# CorePort.net
KiCad netlist of a schematic drawn in Altium Designer
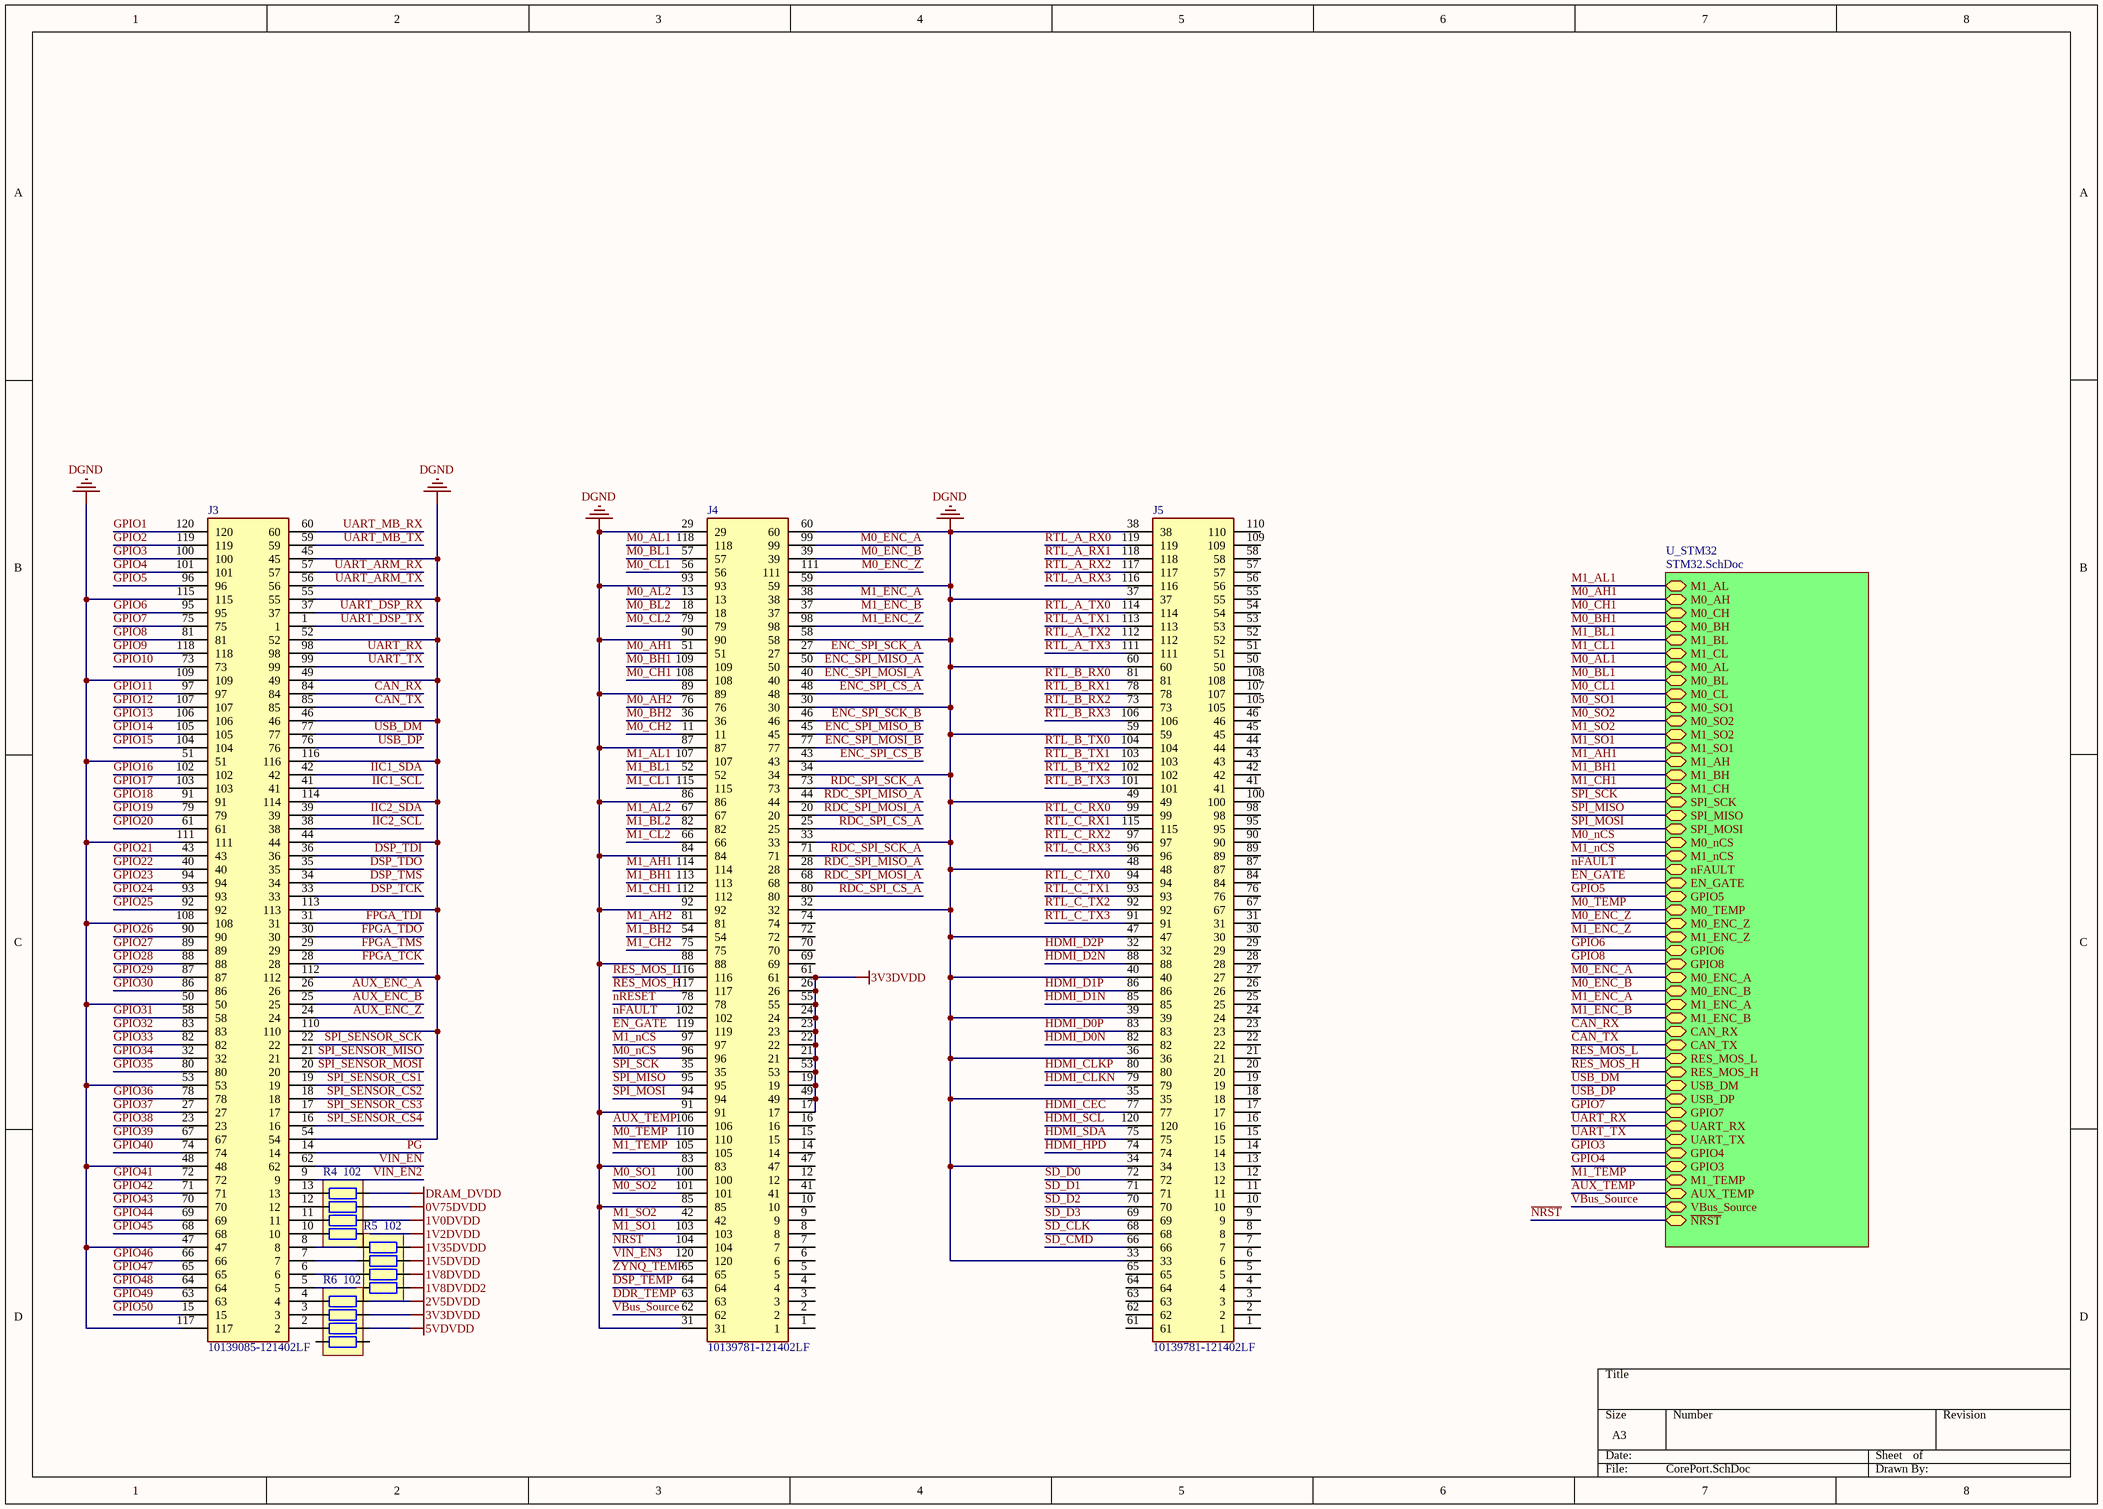
[diagram p0: CorePort.SchDoc]

(export (version "E")
  (design (tool "Eeschema 10.0.6"))
  (components
    (comp (ref "J3")
      (value "10139085-121402LF")
      (footprint "10139085121402LF")
      (description "Connector FE")
      (fields (field (name "MANUFACTURER_PART_NUMBER") "10139781-121402LF"))
      (libsource (lib "SkylakeADSchLib") (part "10139085-121402LF"))
    )
    (comp (ref "J4")
      (value "10139781-121402LF")
      (footprint "SkylakeADPcbLib:10139781121402LF")
      (description "Connector M")
      (libsource (lib "SkylakeADSchLib") (part "10139781-121402LF"))
    )
    (comp (ref "J5")
      (value "10139781-121402LF")
      (footprint "SkylakeADPcbLib:10139781121402LF")
      (description "Connector M")
      (libsource (lib "") (part "10139781-121402LF_1"))
    )
    (comp (ref "R4")
      (value "102")
      (footprint "RCA-8P4R-0603")
      (description "贴片排阻")
      (fields (field (name "版权归属") "封装库来自淘宝 ID：黄晶宝石"))
      (libsource (lib "0.1 - 电阻-电容-电感") (part "R-8P4R"))
    )
    (comp (ref "R5")
      (value "102")
      (footprint "RCA-8P4R-0603")
      (description "贴片排阻")
      (fields (field (name "版权归属") "封装库来自淘宝 ID：黄晶宝石"))
      (libsource (lib "0.1 - 电阻-电容-电感") (part "R-8P4R"))
    )
    (comp (ref "R6")
      (value "102")
      (footprint "RCA-8P4R-0603")
      (description "贴片排阻")
      (fields (field (name "版权归属") "封装库来自淘宝 ID：黄晶宝石"))
      (libsource (lib "0.1 - 电阻-电容-电感") (part "R-8P4R"))
    )
  )
  (nets
    (net (code "1") (name "/AUX_ENC_A") (class "Default")
      (node (ref "J3") (pin "26") (pinfunction "26_26") (pintype "passive"))
    )
    (net (code "2") (name "/AUX_ENC_B") (class "Default")
      (node (ref "J3") (pin "25") (pinfunction "25_25") (pintype "passive"))
    )
    (net (code "3") (name "/AUX_ENC_Z") (class "Default")
      (node (ref "J3") (pin "24") (pinfunction "24_24") (pintype "passive"))
    )
    (net (code "4") (name "/AUX_TEMP") (class "Default")
      (node (ref "J4") (pin "106") (pinfunction "106_106") (pintype "passive"))
    )
    (net (code "5") (name "/CAN_RX") (class "Default")
      (node (ref "J3") (pin "84") (pinfunction "84_84") (pintype "passive"))
    )
    (net (code "6") (name "/CAN_TX") (class "Default")
      (node (ref "J3") (pin "85") (pinfunction "85_85") (pintype "passive"))
    )
    (net (code "7") (name "/DDR_TEMP") (class "Default")
      (node (ref "J4") (pin "63") (pinfunction "63_63") (pintype "passive"))
    )
    (net (code "8") (name "/DSP_TCK") (class "Default")
      (node (ref "J3") (pin "33") (pinfunction "33_33") (pintype "passive"))
    )
    (net (code "9") (name "/DSP_TDI") (class "Default")
      (node (ref "J3") (pin "36") (pinfunction "36_36") (pintype "passive"))
    )
    (net (code "10") (name "/DSP_TDO") (class "Default")
      (node (ref "J3") (pin "35") (pinfunction "35_35") (pintype "passive"))
    )
    (net (code "11") (name "/DSP_TEMP") (class "Default")
      (node (ref "J4") (pin "64") (pinfunction "64_64") (pintype "passive"))
    )
    (net (code "12") (name "/DSP_TMS") (class "Default")
      (node (ref "J3") (pin "34") (pinfunction "34_34") (pintype "passive"))
    )
    (net (code "13") (name "/ENC_SPI_CS_A") (class "Default")
      (node (ref "J4") (pin "48") (pinfunction "48_48") (pintype "passive"))
    )
    (net (code "14") (name "/ENC_SPI_CS_B") (class "Default")
      (node (ref "J4") (pin "43") (pinfunction "43_43") (pintype "passive"))
    )
    (net (code "15") (name "/ENC_SPI_MISO_A") (class "Default")
      (node (ref "J4") (pin "50") (pinfunction "50_50") (pintype "passive"))
    )
    (net (code "16") (name "/ENC_SPI_MISO_B") (class "Default")
      (node (ref "J4") (pin "45") (pinfunction "45_45") (pintype "passive"))
    )
    (net (code "17") (name "/ENC_SPI_MOSI_A") (class "Default")
      (node (ref "J4") (pin "40") (pinfunction "40_40") (pintype "passive"))
    )
    (net (code "18") (name "/ENC_SPI_MOSI_B") (class "Default")
      (node (ref "J4") (pin "77") (pinfunction "77_77") (pintype "passive"))
    )
    (net (code "19") (name "/ENC_SPI_SCK_A") (class "Default")
      (node (ref "J4") (pin "27") (pinfunction "27_27") (pintype "passive"))
    )
    (net (code "20") (name "/ENC_SPI_SCK_B") (class "Default")
      (node (ref "J4") (pin "46") (pinfunction "46_46") (pintype "passive"))
    )
    (net (code "21") (name "/EN_GATE") (class "Default")
      (node (ref "J4") (pin "119") (pinfunction "119_119") (pintype "passive"))
    )
    (net (code "22") (name "/FPGA_TCK") (class "Default")
      (node (ref "J3") (pin "28") (pinfunction "28_28") (pintype "passive"))
    )
    (net (code "23") (name "/FPGA_TDI") (class "Default")
      (node (ref "J3") (pin "31") (pinfunction "31_31") (pintype "passive"))
    )
    (net (code "24") (name "/FPGA_TDO") (class "Default")
      (node (ref "J3") (pin "30") (pinfunction "30_30") (pintype "passive"))
    )
    (net (code "25") (name "/FPGA_TMS") (class "Default")
      (node (ref "J3") (pin "29") (pinfunction "29_29") (pintype "passive"))
    )
    (net (code "26") (name "/GPIO1") (class "Default")
      (node (ref "J3") (pin "120") (pinfunction "120_120") (pintype "passive"))
    )
    (net (code "27") (name "/GPIO2") (class "Default")
      (node (ref "J3") (pin "119") (pinfunction "119_119") (pintype "passive"))
    )
    (net (code "28") (name "/GPIO3") (class "Default")
      (node (ref "J3") (pin "100") (pinfunction "100_100") (pintype "passive"))
    )
    (net (code "29") (name "/GPIO4") (class "Default")
      (node (ref "J3") (pin "101") (pinfunction "101_101") (pintype "passive"))
    )
    (net (code "30") (name "/GPIO5") (class "Default")
      (node (ref "J3") (pin "96") (pinfunction "96_96") (pintype "passive"))
    )
    (net (code "31") (name "/GPIO6") (class "Default")
      (node (ref "J3") (pin "95") (pinfunction "95_95") (pintype "passive"))
    )
    (net (code "32") (name "/GPIO7") (class "Default")
      (node (ref "J3") (pin "75") (pinfunction "75_75") (pintype "passive"))
    )
    (net (code "33") (name "/GPIO8") (class "Default")
      (node (ref "J3") (pin "81") (pinfunction "81_81") (pintype "passive"))
    )
    (net (code "34") (name "/GPIO9") (class "Default")
      (node (ref "J3") (pin "118") (pinfunction "118_118") (pintype "passive"))
    )
    (net (code "35") (name "/GPIO10") (class "Default")
      (node (ref "J3") (pin "73") (pinfunction "73_73") (pintype "passive"))
    )
    (net (code "36") (name "/GPIO11") (class "Default")
      (node (ref "J3") (pin "97") (pinfunction "97_97") (pintype "passive"))
    )
    (net (code "37") (name "/GPIO12") (class "Default")
      (node (ref "J3") (pin "107") (pinfunction "107_107") (pintype "passive"))
    )
    (net (code "38") (name "/GPIO13") (class "Default")
      (node (ref "J3") (pin "106") (pinfunction "106_106") (pintype "passive"))
    )
    (net (code "39") (name "/GPIO14") (class "Default")
      (node (ref "J3") (pin "105") (pinfunction "105_105") (pintype "passive"))
    )
    (net (code "40") (name "/GPIO15") (class "Default")
      (node (ref "J3") (pin "104") (pinfunction "104_104") (pintype "passive"))
    )
    (net (code "41") (name "/GPIO16") (class "Default")
      (node (ref "J3") (pin "102") (pinfunction "102_102") (pintype "passive"))
    )
    (net (code "42") (name "/GPIO17") (class "Default")
      (node (ref "J3") (pin "103") (pinfunction "103_103") (pintype "passive"))
    )
    (net (code "43") (name "/GPIO18") (class "Default")
      (node (ref "J3") (pin "91") (pinfunction "91_91") (pintype "passive"))
    )
    (net (code "44") (name "/GPIO19") (class "Default")
      (node (ref "J3") (pin "79") (pinfunction "79_79") (pintype "passive"))
    )
    (net (code "45") (name "/GPIO20") (class "Default")
      (node (ref "J3") (pin "61") (pinfunction "61_61") (pintype "passive"))
    )
    (net (code "46") (name "/GPIO21") (class "Default")
      (node (ref "J3") (pin "43") (pinfunction "43_43") (pintype "passive"))
    )
    (net (code "47") (name "/GPIO22") (class "Default")
      (node (ref "J3") (pin "40") (pinfunction "40_40") (pintype "passive"))
    )
    (net (code "48") (name "/GPIO23") (class "Default")
      (node (ref "J3") (pin "94") (pinfunction "94_94") (pintype "passive"))
    )
    (net (code "49") (name "/GPIO24") (class "Default")
      (node (ref "J3") (pin "93") (pinfunction "93_93") (pintype "passive"))
    )
    (net (code "50") (name "/GPIO25") (class "Default")
      (node (ref "J3") (pin "92") (pinfunction "92_92") (pintype "passive"))
    )
    (net (code "51") (name "/GPIO26") (class "Default")
      (node (ref "J3") (pin "90") (pinfunction "90_90") (pintype "passive"))
    )
    (net (code "52") (name "/GPIO27") (class "Default")
      (node (ref "J3") (pin "89") (pinfunction "89_89") (pintype "passive"))
    )
    (net (code "53") (name "/GPIO28") (class "Default")
      (node (ref "J3") (pin "88") (pinfunction "88_88") (pintype "passive"))
    )
    (net (code "54") (name "/GPIO29") (class "Default")
      (node (ref "J3") (pin "87") (pinfunction "87_87") (pintype "passive"))
    )
    (net (code "55") (name "/GPIO30") (class "Default")
      (node (ref "J3") (pin "86") (pinfunction "86_86") (pintype "passive"))
    )
    (net (code "56") (name "/GPIO31") (class "Default")
      (node (ref "J3") (pin "58") (pinfunction "58_58") (pintype "passive"))
    )
    (net (code "57") (name "/GPIO32") (class "Default")
      (node (ref "J3") (pin "83") (pinfunction "83_83") (pintype "passive"))
    )
    (net (code "58") (name "/GPIO33") (class "Default")
      (node (ref "J3") (pin "82") (pinfunction "82_82") (pintype "passive"))
    )
    (net (code "59") (name "/GPIO34") (class "Default")
      (node (ref "J3") (pin "32") (pinfunction "32_32") (pintype "passive"))
    )
    (net (code "60") (name "/GPIO35") (class "Default")
      (node (ref "J3") (pin "80") (pinfunction "80_80") (pintype "passive"))
    )
    (net (code "61") (name "/GPIO36") (class "Default")
      (node (ref "J3") (pin "78") (pinfunction "78_78") (pintype "passive"))
    )
    (net (code "62") (name "/GPIO37") (class "Default")
      (node (ref "J3") (pin "27") (pinfunction "27_27") (pintype "passive"))
    )
    (net (code "63") (name "/GPIO38") (class "Default")
      (node (ref "J3") (pin "23") (pinfunction "23_23") (pintype "passive"))
    )
    (net (code "64") (name "/GPIO39") (class "Default")
      (node (ref "J3") (pin "67") (pinfunction "67_67") (pintype "passive"))
    )
    (net (code "65") (name "/GPIO40") (class "Default")
      (node (ref "J3") (pin "74") (pinfunction "74_74") (pintype "passive"))
    )
    (net (code "66") (name "/GPIO41") (class "Default")
      (node (ref "J3") (pin "72") (pinfunction "72_72") (pintype "passive"))
    )
    (net (code "67") (name "/GPIO42") (class "Default")
      (node (ref "J3") (pin "71") (pinfunction "71_71") (pintype "passive"))
    )
    (net (code "68") (name "/GPIO43") (class "Default")
      (node (ref "J3") (pin "70") (pinfunction "70_70") (pintype "passive"))
    )
    (net (code "69") (name "/GPIO44") (class "Default")
      (node (ref "J3") (pin "69") (pinfunction "69_69") (pintype "passive"))
    )
    (net (code "70") (name "/GPIO45") (class "Default")
      (node (ref "J3") (pin "68") (pinfunction "68_68") (pintype "passive"))
    )
    (net (code "71") (name "/GPIO46") (class "Default")
      (node (ref "J3") (pin "66") (pinfunction "66_66") (pintype "passive"))
    )
    (net (code "72") (name "/GPIO47") (class "Default")
      (node (ref "J3") (pin "65") (pinfunction "65_65") (pintype "passive"))
    )
    (net (code "73") (name "/GPIO48") (class "Default")
      (node (ref "J3") (pin "64") (pinfunction "64_64") (pintype "passive"))
    )
    (net (code "74") (name "/GPIO49") (class "Default")
      (node (ref "J3") (pin "63") (pinfunction "63_63") (pintype "passive"))
    )
    (net (code "75") (name "/GPIO50") (class "Default")
      (node (ref "J3") (pin "15") (pinfunction "15_15") (pintype "passive"))
    )
    (net (code "76") (name "/HDMI_CEC") (class "Default")
      (node (ref "J5") (pin "77") (pinfunction "77_77") (pintype "passive"))
    )
    (net (code "77") (name "/HDMI_CLKN") (class "Default")
      (node (ref "J5") (pin "79") (pinfunction "79_79") (pintype "passive"))
    )
    (net (code "78") (name "/HDMI_CLKP") (class "Default")
      (node (ref "J5") (pin "80") (pinfunction "80_80") (pintype "passive"))
    )
    (net (code "79") (name "/HDMI_D0N") (class "Default")
      (node (ref "J5") (pin "82") (pinfunction "82_82") (pintype "passive"))
    )
    (net (code "80") (name "/HDMI_D0P") (class "Default")
      (node (ref "J5") (pin "83") (pinfunction "83_83") (pintype "passive"))
    )
    (net (code "81") (name "/HDMI_D1N") (class "Default")
      (node (ref "J5") (pin "85") (pinfunction "85_85") (pintype "passive"))
    )
    (net (code "82") (name "/HDMI_D1P") (class "Default")
      (node (ref "J5") (pin "86") (pinfunction "86_86") (pintype "passive"))
    )
    (net (code "83") (name "/HDMI_D2N") (class "Default")
      (node (ref "J5") (pin "88") (pinfunction "88_88") (pintype "passive"))
    )
    (net (code "84") (name "/HDMI_D2P") (class "Default")
      (node (ref "J5") (pin "32") (pinfunction "32_32") (pintype "passive"))
    )
    (net (code "85") (name "/HDMI_HPD") (class "Default")
      (node (ref "J5") (pin "74") (pinfunction "74_74") (pintype "passive"))
    )
    (net (code "86") (name "/HDMI_SCL") (class "Default")
      (node (ref "J5") (pin "120") (pinfunction "120_120") (pintype "passive"))
    )
    (net (code "87") (name "/HDMI_SDA") (class "Default")
      (node (ref "J5") (pin "75") (pinfunction "75_75") (pintype "passive"))
    )
    (net (code "88") (name "/IIC1_SCL") (class "Default")
      (node (ref "J3") (pin "41") (pinfunction "41_41") (pintype "passive"))
    )
    (net (code "89") (name "/IIC1_SDA") (class "Default")
      (node (ref "J3") (pin "42") (pinfunction "42_42") (pintype "passive"))
    )
    (net (code "90") (name "/IIC2_SCL") (class "Default")
      (node (ref "J3") (pin "38") (pinfunction "38_38") (pintype "passive"))
    )
    (net (code "91") (name "/IIC2_SDA") (class "Default")
      (node (ref "J3") (pin "39") (pinfunction "39_39") (pintype "passive"))
    )
    (net (code "92") (name "/M0_AH1") (class "Default")
      (node (ref "J4") (pin "51") (pinfunction "51_51") (pintype "passive"))
    )
    (net (code "93") (name "/M0_AH2") (class "Default")
      (node (ref "J4") (pin "76") (pinfunction "76_76") (pintype "passive"))
    )
    (net (code "94") (name "/M0_AL1") (class "Default")
      (node (ref "J4") (pin "118") (pinfunction "118_118") (pintype "passive"))
    )
    (net (code "95") (name "/M0_AL2") (class "Default")
      (node (ref "J4") (pin "13") (pinfunction "13_13") (pintype "passive"))
    )
    (net (code "96") (name "/M0_BH1") (class "Default")
      (node (ref "J4") (pin "109") (pinfunction "109_109") (pintype "passive"))
    )
    (net (code "97") (name "/M0_BH2") (class "Default")
      (node (ref "J4") (pin "36") (pinfunction "36_36") (pintype "passive"))
    )
    (net (code "98") (name "/M0_BL1") (class "Default")
      (node (ref "J4") (pin "57") (pinfunction "57_57") (pintype "passive"))
    )
    (net (code "99") (name "/M0_BL2") (class "Default")
      (node (ref "J4") (pin "18") (pinfunction "18_18") (pintype "passive"))
    )
    (net (code "100") (name "/M0_CH1") (class "Default")
      (node (ref "J4") (pin "108") (pinfunction "108_108") (pintype "passive"))
    )
    (net (code "101") (name "/M0_CH2") (class "Default")
      (node (ref "J4") (pin "11") (pinfunction "11_11") (pintype "passive"))
    )
    (net (code "102") (name "/M0_CL1") (class "Default")
      (node (ref "J4") (pin "56") (pinfunction "56_56") (pintype "passive"))
    )
    (net (code "103") (name "/M0_CL2") (class "Default")
      (node (ref "J4") (pin "79") (pinfunction "79_79") (pintype "passive"))
    )
    (net (code "104") (name "/M0_ENC_A") (class "Default")
      (node (ref "J4") (pin "99") (pinfunction "99_99") (pintype "passive"))
    )
    (net (code "105") (name "/M0_ENC_B") (class "Default")
      (node (ref "J4") (pin "39") (pinfunction "39_39") (pintype "passive"))
    )
    (net (code "106") (name "/M0_ENC_Z") (class "Default")
      (node (ref "J4") (pin "111") (pinfunction "111_111") (pintype "passive"))
    )
    (net (code "107") (name "/M0_SO1") (class "Default")
      (node (ref "J4") (pin "100") (pinfunction "100_100") (pintype "passive"))
    )
    (net (code "108") (name "/M0_SO2") (class "Default")
      (node (ref "J4") (pin "101") (pinfunction "101_101") (pintype "passive"))
    )
    (net (code "109") (name "/M0_TEMP") (class "Default")
      (node (ref "J4") (pin "110") (pinfunction "110_110") (pintype "passive"))
    )
    (net (code "110") (name "/M0_nCS") (class "Default")
      (node (ref "J4") (pin "96") (pinfunction "96_96") (pintype "passive"))
    )
    (net (code "111") (name "/M1_AH1") (class "Default")
      (node (ref "J4") (pin "114") (pinfunction "114_114") (pintype "passive"))
    )
    (net (code "112") (name "/M1_AH2") (class "Default")
      (node (ref "J4") (pin "81") (pinfunction "81_81") (pintype "passive"))
    )
    (net (code "113") (name "/M1_AL1") (class "Default")
      (node (ref "J4") (pin "107") (pinfunction "107_107") (pintype "passive"))
    )
    (net (code "114") (name "/M1_AL2") (class "Default")
      (node (ref "J4") (pin "67") (pinfunction "67_67") (pintype "passive"))
    )
    (net (code "115") (name "/M1_BH1") (class "Default")
      (node (ref "J4") (pin "113") (pinfunction "113_113") (pintype "passive"))
    )
    (net (code "116") (name "/M1_BH2") (class "Default")
      (node (ref "J4") (pin "54") (pinfunction "54_54") (pintype "passive"))
    )
    (net (code "117") (name "/M1_BL1") (class "Default")
      (node (ref "J4") (pin "52") (pinfunction "52_52") (pintype "passive"))
    )
    (net (code "118") (name "/M1_BL2") (class "Default")
      (node (ref "J4") (pin "82") (pinfunction "82_82") (pintype "passive"))
    )
    (net (code "119") (name "/M1_CH1") (class "Default")
      (node (ref "J4") (pin "112") (pinfunction "112_112") (pintype "passive"))
    )
    (net (code "120") (name "/M1_CH2") (class "Default")
      (node (ref "J4") (pin "75") (pinfunction "75_75") (pintype "passive"))
    )
    (net (code "121") (name "/M1_CL1") (class "Default")
      (node (ref "J4") (pin "115") (pinfunction "115_115") (pintype "passive"))
    )
    (net (code "122") (name "/M1_CL2") (class "Default")
      (node (ref "J4") (pin "66") (pinfunction "66_66") (pintype "passive"))
    )
    (net (code "123") (name "/M1_ENC_A") (class "Default")
      (node (ref "J4") (pin "38") (pinfunction "38_38") (pintype "passive"))
    )
    (net (code "124") (name "/M1_ENC_B") (class "Default")
      (node (ref "J4") (pin "37") (pinfunction "37_37") (pintype "passive"))
    )
    (net (code "125") (name "/M1_ENC_Z") (class "Default")
      (node (ref "J4") (pin "98") (pinfunction "98_98") (pintype "passive"))
    )
    (net (code "126") (name "/M1_SO1") (class "Default")
      (node (ref "J4") (pin "103") (pinfunction "103_103") (pintype "passive"))
    )
    (net (code "127") (name "/M1_SO2") (class "Default")
      (node (ref "J4") (pin "42") (pinfunction "42_42") (pintype "passive"))
    )
    (net (code "128") (name "/M1_TEMP") (class "Default")
      (node (ref "J4") (pin "105") (pinfunction "105_105") (pintype "passive"))
    )
    (net (code "129") (name "/M1_nCS") (class "Default")
      (node (ref "J4") (pin "97") (pinfunction "97_97") (pintype "passive"))
    )
    (net (code "130") (name "/PG") (class "Default")
      (node (ref "J3") (pin "14") (pinfunction "14_14") (pintype "passive"))
    )
    (net (code "131") (name "/RDC_SPI_CS_A") (class "Default")
      (node (ref "J4") (pin "25") (pinfunction "25_25") (pintype "passive"))
      (node (ref "J4") (pin "80") (pinfunction "80_80") (pintype "passive"))
    )
    (net (code "132") (name "/RDC_SPI_MISO_A") (class "Default")
      (node (ref "J4") (pin "28") (pinfunction "28_28") (pintype "passive"))
      (node (ref "J4") (pin "44") (pinfunction "44_44") (pintype "passive"))
    )
    (net (code "133") (name "/RDC_SPI_MOSI_A") (class "Default")
      (node (ref "J4") (pin "20") (pinfunction "20_20") (pintype "passive"))
      (node (ref "J4") (pin "68") (pinfunction "68_68") (pintype "passive"))
    )
    (net (code "134") (name "/RDC_SPI_SCK_A") (class "Default")
      (node (ref "J4") (pin "71") (pinfunction "71_71") (pintype "passive"))
      (node (ref "J4") (pin "73") (pinfunction "73_73") (pintype "passive"))
    )
    (net (code "135") (name "/RES_MOS_H") (class "Default")
      (node (ref "J4") (pin "117") (pinfunction "117_117") (pintype "passive"))
    )
    (net (code "136") (name "/RES_MOS_L") (class "Default")
      (node (ref "J4") (pin "116") (pinfunction "116_116") (pintype "passive"))
    )
    (net (code "137") (name "/RTL_A_RX0") (class "Default")
      (node (ref "J5") (pin "119") (pinfunction "119_119") (pintype "passive"))
    )
    (net (code "138") (name "/RTL_A_RX1") (class "Default")
      (node (ref "J5") (pin "118") (pinfunction "118_118") (pintype "passive"))
    )
    (net (code "139") (name "/RTL_A_RX2") (class "Default")
      (node (ref "J5") (pin "117") (pinfunction "117_117") (pintype "passive"))
    )
    (net (code "140") (name "/RTL_A_RX3") (class "Default")
      (node (ref "J5") (pin "116") (pinfunction "116_116") (pintype "passive"))
    )
    (net (code "141") (name "/RTL_A_TX0") (class "Default")
      (node (ref "J5") (pin "114") (pinfunction "114_114") (pintype "passive"))
    )
    (net (code "142") (name "/RTL_A_TX1") (class "Default")
      (node (ref "J5") (pin "113") (pinfunction "113_113") (pintype "passive"))
    )
    (net (code "143") (name "/RTL_A_TX2") (class "Default")
      (node (ref "J5") (pin "112") (pinfunction "112_112") (pintype "passive"))
    )
    (net (code "144") (name "/RTL_A_TX3") (class "Default")
      (node (ref "J5") (pin "111") (pinfunction "111_111") (pintype "passive"))
    )
    (net (code "145") (name "/RTL_B_RX0") (class "Default")
      (node (ref "J5") (pin "81") (pinfunction "81_81") (pintype "passive"))
    )
    (net (code "146") (name "/RTL_B_RX1") (class "Default")
      (node (ref "J5") (pin "78") (pinfunction "78_78") (pintype "passive"))
    )
    (net (code "147") (name "/RTL_B_RX2") (class "Default")
      (node (ref "J5") (pin "73") (pinfunction "73_73") (pintype "passive"))
    )
    (net (code "148") (name "/RTL_B_RX3") (class "Default")
      (node (ref "J5") (pin "106") (pinfunction "106_106") (pintype "passive"))
    )
    (net (code "149") (name "/RTL_B_TX0") (class "Default")
      (node (ref "J5") (pin "104") (pinfunction "104_104") (pintype "passive"))
    )
    (net (code "150") (name "/RTL_B_TX1") (class "Default")
      (node (ref "J5") (pin "103") (pinfunction "103_103") (pintype "passive"))
    )
    (net (code "151") (name "/RTL_B_TX2") (class "Default")
      (node (ref "J5") (pin "102") (pinfunction "102_102") (pintype "passive"))
    )
    (net (code "152") (name "/RTL_B_TX3") (class "Default")
      (node (ref "J5") (pin "101") (pinfunction "101_101") (pintype "passive"))
    )
    (net (code "153") (name "/RTL_C_RX0") (class "Default")
      (node (ref "J5") (pin "99") (pinfunction "99_99") (pintype "passive"))
    )
    (net (code "154") (name "/RTL_C_RX1") (class "Default")
      (node (ref "J5") (pin "115") (pinfunction "115_115") (pintype "passive"))
    )
    (net (code "155") (name "/RTL_C_RX2") (class "Default")
      (node (ref "J5") (pin "97") (pinfunction "97_97") (pintype "passive"))
    )
    (net (code "156") (name "/RTL_C_RX3") (class "Default")
      (node (ref "J5") (pin "96") (pinfunction "96_96") (pintype "passive"))
    )
    (net (code "157") (name "/RTL_C_TX0") (class "Default")
      (node (ref "J5") (pin "94") (pinfunction "94_94") (pintype "passive"))
    )
    (net (code "158") (name "/RTL_C_TX1") (class "Default")
      (node (ref "J5") (pin "93") (pinfunction "93_93") (pintype "passive"))
    )
    (net (code "159") (name "/RTL_C_TX2") (class "Default")
      (node (ref "J5") (pin "92") (pinfunction "92_92") (pintype "passive"))
    )
    (net (code "160") (name "/RTL_C_TX3") (class "Default")
      (node (ref "J5") (pin "91") (pinfunction "91_91") (pintype "passive"))
    )
    (net (code "161") (name "/SD_CLK") (class "Default")
      (node (ref "J5") (pin "68") (pinfunction "68_68") (pintype "passive"))
    )
    (net (code "162") (name "/SD_CMD") (class "Default")
      (node (ref "J5") (pin "66") (pinfunction "66_66") (pintype "passive"))
    )
    (net (code "163") (name "/SD_D0") (class "Default")
      (node (ref "J5") (pin "72") (pinfunction "72_72") (pintype "passive"))
    )
    (net (code "164") (name "/SD_D1") (class "Default")
      (node (ref "J5") (pin "71") (pinfunction "71_71") (pintype "passive"))
    )
    (net (code "165") (name "/SD_D2") (class "Default")
      (node (ref "J5") (pin "70") (pinfunction "70_70") (pintype "passive"))
    )
    (net (code "166") (name "/SD_D3") (class "Default")
      (node (ref "J5") (pin "69") (pinfunction "69_69") (pintype "passive"))
    )
    (net (code "167") (name "/SPI_MISO") (class "Default")
      (node (ref "J4") (pin "95") (pinfunction "95_95") (pintype "passive"))
    )
    (net (code "168") (name "/SPI_MOSI") (class "Default")
      (node (ref "J4") (pin "94") (pinfunction "94_94") (pintype "passive"))
    )
    (net (code "169") (name "/SPI_SCK") (class "Default")
      (node (ref "J4") (pin "35") (pinfunction "35_35") (pintype "passive"))
    )
    (net (code "170") (name "/SPI_SENSOR_CS1") (class "Default")
      (node (ref "J3") (pin "19") (pinfunction "19_19") (pintype "passive"))
    )
    (net (code "171") (name "/SPI_SENSOR_CS2") (class "Default")
      (node (ref "J3") (pin "18") (pinfunction "18_18") (pintype "passive"))
    )
    (net (code "172") (name "/SPI_SENSOR_CS3") (class "Default")
      (node (ref "J3") (pin "17") (pinfunction "17_17") (pintype "passive"))
    )
    (net (code "173") (name "/SPI_SENSOR_CS4") (class "Default")
      (node (ref "J3") (pin "16") (pinfunction "16_16") (pintype "passive"))
    )
    (net (code "174") (name "/SPI_SENSOR_MISO") (class "Default")
      (node (ref "J3") (pin "21") (pinfunction "21_21") (pintype "passive"))
    )
    (net (code "175") (name "/SPI_SENSOR_MOSI") (class "Default")
      (node (ref "J3") (pin "20") (pinfunction "20_20") (pintype "passive"))
    )
    (net (code "176") (name "/SPI_SENSOR_SCK") (class "Default")
      (node (ref "J3") (pin "22") (pinfunction "22_22") (pintype "passive"))
    )
    (net (code "177") (name "/UART_ARM_RX") (class "Default")
      (node (ref "J3") (pin "57") (pinfunction "57_57") (pintype "passive"))
    )
    (net (code "178") (name "/UART_ARM_TX") (class "Default")
      (node (ref "J3") (pin "56") (pinfunction "56_56") (pintype "passive"))
    )
    (net (code "179") (name "/UART_DSP_RX") (class "Default")
      (node (ref "J3") (pin "37") (pinfunction "37_37") (pintype "passive"))
    )
    (net (code "180") (name "/UART_DSP_TX") (class "Default")
      (node (ref "J3") (pin "1") (pinfunction "1_1") (pintype "passive"))
    )
    (net (code "181") (name "/UART_MB_RX") (class "Default")
      (node (ref "J3") (pin "60") (pinfunction "60_60") (pintype "passive"))
    )
    (net (code "182") (name "/UART_MB_TX") (class "Default")
      (node (ref "J3") (pin "59") (pinfunction "59_59") (pintype "passive"))
    )
    (net (code "183") (name "/UART_RX") (class "Default")
      (node (ref "J3") (pin "98") (pinfunction "98_98") (pintype "passive"))
    )
    (net (code "184") (name "/UART_TX") (class "Default")
      (node (ref "J3") (pin "99") (pinfunction "99_99") (pintype "passive"))
    )
    (net (code "185") (name "/USB_DM") (class "Default")
      (node (ref "J3") (pin "77") (pinfunction "77_77") (pintype "passive"))
    )
    (net (code "186") (name "/USB_DP") (class "Default")
      (node (ref "J3") (pin "76") (pinfunction "76_76") (pintype "passive"))
    )
    (net (code "187") (name "/VBus_Source") (class "Default")
      (node (ref "J4") (pin "62") (pinfunction "62_62") (pintype "passive"))
    )
    (net (code "188") (name "/VIN_EN") (class "Default")
      (node (ref "J3") (pin "62") (pinfunction "62_62") (pintype "passive"))
    )
    (net (code "189") (name "/VIN_EN2") (class "Default")
      (node (ref "J3") (pin "9") (pinfunction "9_9") (pintype "passive"))
    )
    (net (code "190") (name "/VIN_EN3") (class "Default")
      (node (ref "J4") (pin "120") (pinfunction "120_120") (pintype "passive"))
    )
    (net (code "191") (name "/ZYNQ_TEMP") (class "Default")
      (node (ref "J4") (pin "65") (pinfunction "65_65") (pintype "passive"))
    )
    (net (code "192") (name "/nFAULT") (class "Default")
      (node (ref "J4") (pin "102") (pinfunction "102_102") (pintype "passive"))
    )
    (net (code "193") (name "/nRESET") (class "Default")
      (node (ref "J4") (pin "78") (pinfunction "78_78") (pintype "passive"))
    )
    (net (code "194") (name "/~{NRST}") (class "Default")
      (node (ref "J4") (pin "104") (pinfunction "104_104") (pintype "passive"))
    )
    (net (code "195") (name "0V75DVDD") (class "Default")
      (node (ref "R4") (pin "7") (pinfunction "7_7") (pintype "passive"))
    )
    (net (code "196") (name "1V0DVDD") (class "Default")
      (node (ref "R4") (pin "6") (pinfunction "6_6") (pintype "passive"))
    )
    (net (code "197") (name "1V2DVDD") (class "Default")
      (node (ref "R4") (pin "5") (pinfunction "5_5") (pintype "passive"))
    )
    (net (code "198") (name "1V5DVDD") (class "Default")
      (node (ref "R5") (pin "7") (pinfunction "7_7") (pintype "passive"))
    )
    (net (code "199") (name "1V8DVDD") (class "Default")
      (node (ref "R5") (pin "6") (pinfunction "6_6") (pintype "passive"))
    )
    (net (code "200") (name "1V8DVDD2") (class "Default")
      (node (ref "R5") (pin "5") (pinfunction "5_5") (pintype "passive"))
    )
    (net (code "201") (name "1V35DVDD") (class "Default")
      (node (ref "R5") (pin "8") (pinfunction "8_8") (pintype "passive"))
    )
    (net (code "202") (name "2V5DVDD") (class "Default")
      (node (ref "R6") (pin "8") (pinfunction "8_8") (pintype "passive"))
    )
    (net (code "203") (name "3V3DVDD") (class "Default")
      (node (ref "J4") (pin "17") (pinfunction "17_17") (pintype "passive"))
      (node (ref "J4") (pin "19") (pinfunction "19_19") (pintype "passive"))
      (node (ref "J4") (pin "21") (pinfunction "21_21") (pintype "passive"))
      (node (ref "J4") (pin "22") (pinfunction "22_22") (pintype "passive"))
      (node (ref "J4") (pin "23") (pinfunction "23_23") (pintype "passive"))
      (node (ref "J4") (pin "24") (pinfunction "24_24") (pintype "passive"))
      (node (ref "J4") (pin "26") (pinfunction "26_26") (pintype "passive"))
      (node (ref "J4") (pin "49") (pinfunction "49_49") (pintype "passive"))
      (node (ref "J4") (pin "53") (pinfunction "53_53") (pintype "passive"))
      (node (ref "J4") (pin "55") (pinfunction "55_55") (pintype "passive"))
      (node (ref "J4") (pin "61") (pinfunction "61_61") (pintype "passive"))
      (node (ref "R6") (pin "7") (pinfunction "7_7") (pintype "passive"))
    )
    (net (code "204") (name "5VDVDD") (class "Default")
      (node (ref "R6") (pin "6") (pinfunction "6_6") (pintype "passive"))
    )
    (net (code "205") (name "DGND") (class "Default")
      (node (ref "J3") (pin "108") (pinfunction "108_108") (pintype "passive"))
      (node (ref "J3") (pin "109") (pinfunction "109_109") (pintype "passive"))
      (node (ref "J3") (pin "110") (pinfunction "110_110") (pintype "passive"))
      (node (ref "J3") (pin "111") (pinfunction "111_111") (pintype "passive"))
      (node (ref "J3") (pin "112") (pinfunction "112_112") (pintype "passive"))
      (node (ref "J3") (pin "113") (pinfunction "113_113") (pintype "passive"))
      (node (ref "J3") (pin "114") (pinfunction "114_114") (pintype "passive"))
      (node (ref "J3") (pin "115") (pinfunction "115_115") (pintype "passive"))
      (node (ref "J3") (pin "116") (pinfunction "116_116") (pintype "passive"))
      (node (ref "J3") (pin "117") (pinfunction "117_117") (pintype "passive"))
      (node (ref "J3") (pin "44") (pinfunction "44_44") (pintype "passive"))
      (node (ref "J3") (pin "45") (pinfunction "45_45") (pintype "passive"))
      (node (ref "J3") (pin "46") (pinfunction "46_46") (pintype "passive"))
      (node (ref "J3") (pin "47") (pinfunction "47_47") (pintype "passive"))
      (node (ref "J3") (pin "48") (pinfunction "48_48") (pintype "passive"))
      (node (ref "J3") (pin "49") (pinfunction "49_49") (pintype "passive"))
      (node (ref "J3") (pin "50") (pinfunction "50_50") (pintype "passive"))
      (node (ref "J3") (pin "51") (pinfunction "51_51") (pintype "passive"))
      (node (ref "J3") (pin "52") (pinfunction "52_52") (pintype "passive"))
      (node (ref "J3") (pin "53") (pinfunction "53_53") (pintype "passive"))
      (node (ref "J3") (pin "54") (pinfunction "54_54") (pintype "passive"))
      (node (ref "J3") (pin "55") (pinfunction "55_55") (pintype "passive"))
      (node (ref "J4") (pin "29") (pinfunction "29_29") (pintype "passive"))
      (node (ref "J4") (pin "30") (pinfunction "30_30") (pintype "passive"))
      (node (ref "J4") (pin "31") (pinfunction "31_31") (pintype "passive"))
      (node (ref "J4") (pin "32") (pinfunction "32_32") (pintype "passive"))
      (node (ref "J4") (pin "33") (pinfunction "33_33") (pintype "passive"))
      (node (ref "J4") (pin "34") (pinfunction "34_34") (pintype "passive"))
      (node (ref "J4") (pin "58") (pinfunction "58_58") (pintype "passive"))
      (node (ref "J4") (pin "59") (pinfunction "59_59") (pintype "passive"))
      (node (ref "J4") (pin "60") (pinfunction "60_60") (pintype "passive"))
      (node (ref "J4") (pin "83") (pinfunction "83_83") (pintype "passive"))
      (node (ref "J4") (pin "84") (pinfunction "84_84") (pintype "passive"))
      (node (ref "J4") (pin "85") (pinfunction "85_85") (pintype "passive"))
      (node (ref "J4") (pin "86") (pinfunction "86_86") (pintype "passive"))
      (node (ref "J4") (pin "87") (pinfunction "87_87") (pintype "passive"))
      (node (ref "J4") (pin "88") (pinfunction "88_88") (pintype "passive"))
      (node (ref "J4") (pin "89") (pinfunction "89_89") (pintype "passive"))
      (node (ref "J4") (pin "90") (pinfunction "90_90") (pintype "passive"))
      (node (ref "J4") (pin "91") (pinfunction "91_91") (pintype "passive"))
      (node (ref "J4") (pin "92") (pinfunction "92_92") (pintype "passive"))
      (node (ref "J4") (pin "93") (pinfunction "93_93") (pintype "passive"))
      (node (ref "J5") (pin "33") (pinfunction "33_33") (pintype "passive"))
      (node (ref "J5") (pin "34") (pinfunction "34_34") (pintype "passive"))
      (node (ref "J5") (pin "35") (pinfunction "35_35") (pintype "passive"))
      (node (ref "J5") (pin "36") (pinfunction "36_36") (pintype "passive"))
      (node (ref "J5") (pin "37") (pinfunction "37_37") (pintype "passive"))
      (node (ref "J5") (pin "38") (pinfunction "38_38") (pintype "passive"))
      (node (ref "J5") (pin "39") (pinfunction "39_39") (pintype "passive"))
      (node (ref "J5") (pin "40") (pinfunction "40_40") (pintype "passive"))
      (node (ref "J5") (pin "47") (pinfunction "47_47") (pintype "passive"))
      (node (ref "J5") (pin "48") (pinfunction "48_48") (pintype "passive"))
      (node (ref "J5") (pin "49") (pinfunction "49_49") (pintype "passive"))
      (node (ref "J5") (pin "59") (pinfunction "59_59") (pintype "passive"))
      (node (ref "J5") (pin "60") (pinfunction "60_60") (pintype "passive"))
    )
    (net (code "206") (name "DRAM_DVDD") (class "Default")
      (node (ref "R4") (pin "8") (pinfunction "8_8") (pintype "passive"))
    )
    (net (code "207") (name "Net-(J3-Pad2)") (class "Default")
      (node (ref "J3") (pin "2") (pinfunction "2_2") (pintype "passive"))
      (node (ref "R6") (pin "3") (pinfunction "3_3") (pintype "passive"))
    )
    (net (code "208") (name "Net-(J3-Pad3)") (class "Default")
      (node (ref "J3") (pin "3") (pinfunction "3_3") (pintype "passive"))
      (node (ref "R6") (pin "2") (pinfunction "2_2") (pintype "passive"))
    )
    (net (code "209") (name "Net-(J3-Pad4)") (class "Default")
      (node (ref "J3") (pin "4") (pinfunction "4_4") (pintype "passive"))
      (node (ref "R6") (pin "1") (pinfunction "1_1") (pintype "passive"))
    )
    (net (code "210") (name "Net-(J3-Pad5)") (class "Default")
      (node (ref "J3") (pin "5") (pinfunction "5_5") (pintype "passive"))
      (node (ref "R5") (pin "4") (pinfunction "4_4") (pintype "passive"))
    )
    (net (code "211") (name "Net-(J3-Pad6)") (class "Default")
      (node (ref "J3") (pin "6") (pinfunction "6_6") (pintype "passive"))
      (node (ref "R5") (pin "3") (pinfunction "3_3") (pintype "passive"))
    )
    (net (code "212") (name "Net-(J3-Pad7)") (class "Default")
      (node (ref "J3") (pin "7") (pinfunction "7_7") (pintype "passive"))
      (node (ref "R5") (pin "2") (pinfunction "2_2") (pintype "passive"))
    )
    (net (code "213") (name "Net-(J3-Pad8)") (class "Default")
      (node (ref "J3") (pin "8") (pinfunction "8_8") (pintype "passive"))
      (node (ref "R5") (pin "1") (pinfunction "1_1") (pintype "passive"))
    )
    (net (code "214") (name "Net-(J3-Pad10)") (class "Default")
      (node (ref "J3") (pin "10") (pinfunction "10_10") (pintype "passive"))
      (node (ref "R4") (pin "4") (pinfunction "4_4") (pintype "passive"))
    )
    (net (code "215") (name "Net-(J3-Pad11)") (class "Default")
      (node (ref "J3") (pin "11") (pinfunction "11_11") (pintype "passive"))
      (node (ref "R4") (pin "3") (pinfunction "3_3") (pintype "passive"))
    )
    (net (code "216") (name "Net-(J3-Pad12)") (class "Default")
      (node (ref "J3") (pin "12") (pinfunction "12_12") (pintype "passive"))
      (node (ref "R4") (pin "2") (pinfunction "2_2") (pintype "passive"))
    )
    (net (code "217") (name "Net-(J3-Pad13)") (class "Default")
      (node (ref "J3") (pin "13") (pinfunction "13_13") (pintype "passive"))
      (node (ref "R4") (pin "1") (pinfunction "1_1") (pintype "passive"))
    )
    (net (code "218") (name "unconnected-(J4-Pad1)") (class "Default")
      (node (ref "J4") (pin "1") (pinfunction "1_1") (pintype "passive"))
    )
    (net (code "219") (name "unconnected-(J4-Pad2)") (class "Default")
      (node (ref "J4") (pin "2") (pinfunction "2_2") (pintype "passive"))
    )
    (net (code "220") (name "unconnected-(J4-Pad3)") (class "Default")
      (node (ref "J4") (pin "3") (pinfunction "3_3") (pintype "passive"))
    )
    (net (code "221") (name "unconnected-(J4-Pad4)") (class "Default")
      (node (ref "J4") (pin "4") (pinfunction "4_4") (pintype "passive"))
    )
    (net (code "222") (name "unconnected-(J4-Pad5)") (class "Default")
      (node (ref "J4") (pin "5") (pinfunction "5_5") (pintype "passive"))
    )
    (net (code "223") (name "unconnected-(J4-Pad6)") (class "Default")
      (node (ref "J4") (pin "6") (pinfunction "6_6") (pintype "passive"))
    )
    (net (code "224") (name "unconnected-(J4-Pad7)") (class "Default")
      (node (ref "J4") (pin "7") (pinfunction "7_7") (pintype "passive"))
    )
    (net (code "225") (name "unconnected-(J4-Pad8)") (class "Default")
      (node (ref "J4") (pin "8") (pinfunction "8_8") (pintype "passive"))
    )
    (net (code "226") (name "unconnected-(J4-Pad9)") (class "Default")
      (node (ref "J4") (pin "9") (pinfunction "9_9") (pintype "passive"))
    )
    (net (code "227") (name "unconnected-(J4-Pad10)") (class "Default")
      (node (ref "J4") (pin "10") (pinfunction "10_10") (pintype "passive"))
    )
    (net (code "228") (name "unconnected-(J4-Pad12)") (class "Default")
      (node (ref "J4") (pin "12") (pinfunction "12_12") (pintype "passive"))
    )
    (net (code "229") (name "unconnected-(J4-Pad14)") (class "Default")
      (node (ref "J4") (pin "14") (pinfunction "14_14") (pintype "passive"))
    )
    (net (code "230") (name "unconnected-(J4-Pad15)") (class "Default")
      (node (ref "J4") (pin "15") (pinfunction "15_15") (pintype "passive"))
    )
    (net (code "231") (name "unconnected-(J4-Pad16)") (class "Default")
      (node (ref "J4") (pin "16") (pinfunction "16_16") (pintype "passive"))
    )
    (net (code "232") (name "unconnected-(J4-Pad41)") (class "Default")
      (node (ref "J4") (pin "41") (pinfunction "41_41") (pintype "passive"))
    )
    (net (code "233") (name "unconnected-(J4-Pad47)") (class "Default")
      (node (ref "J4") (pin "47") (pinfunction "47_47") (pintype "passive"))
    )
    (net (code "234") (name "unconnected-(J4-Pad69)") (class "Default")
      (node (ref "J4") (pin "69") (pinfunction "69_69") (pintype "passive"))
    )
    (net (code "235") (name "unconnected-(J4-Pad70)") (class "Default")
      (node (ref "J4") (pin "70") (pinfunction "70_70") (pintype "passive"))
    )
    (net (code "236") (name "unconnected-(J4-Pad72)") (class "Default")
      (node (ref "J4") (pin "72") (pinfunction "72_72") (pintype "passive"))
    )
    (net (code "237") (name "unconnected-(J4-Pad74)") (class "Default")
      (node (ref "J4") (pin "74") (pinfunction "74_74") (pintype "passive"))
    )
    (net (code "238") (name "unconnected-(J5-Pad1)") (class "Default")
      (node (ref "J5") (pin "1") (pinfunction "1_1") (pintype "passive"))
    )
    (net (code "239") (name "unconnected-(J5-Pad2)") (class "Default")
      (node (ref "J5") (pin "2") (pinfunction "2_2") (pintype "passive"))
    )
    (net (code "240") (name "unconnected-(J5-Pad3)") (class "Default")
      (node (ref "J5") (pin "3") (pinfunction "3_3") (pintype "passive"))
    )
    (net (code "241") (name "unconnected-(J5-Pad4)") (class "Default")
      (node (ref "J5") (pin "4") (pinfunction "4_4") (pintype "passive"))
    )
    (net (code "242") (name "unconnected-(J5-Pad5)") (class "Default")
      (node (ref "J5") (pin "5") (pinfunction "5_5") (pintype "passive"))
    )
    (net (code "243") (name "unconnected-(J5-Pad6)") (class "Default")
      (node (ref "J5") (pin "6") (pinfunction "6_6") (pintype "passive"))
    )
    (net (code "244") (name "unconnected-(J5-Pad7)") (class "Default")
      (node (ref "J5") (pin "7") (pinfunction "7_7") (pintype "passive"))
    )
    (net (code "245") (name "unconnected-(J5-Pad8)") (class "Default")
      (node (ref "J5") (pin "8") (pinfunction "8_8") (pintype "passive"))
    )
    (net (code "246") (name "unconnected-(J5-Pad9)") (class "Default")
      (node (ref "J5") (pin "9") (pinfunction "9_9") (pintype "passive"))
    )
    (net (code "247") (name "unconnected-(J5-Pad10)") (class "Default")
      (node (ref "J5") (pin "10") (pinfunction "10_10") (pintype "passive"))
    )
    (net (code "248") (name "unconnected-(J5-Pad11)") (class "Default")
      (node (ref "J5") (pin "11") (pinfunction "11_11") (pintype "passive"))
    )
    (net (code "249") (name "unconnected-(J5-Pad12)") (class "Default")
      (node (ref "J5") (pin "12") (pinfunction "12_12") (pintype "passive"))
    )
    (net (code "250") (name "unconnected-(J5-Pad13)") (class "Default")
      (node (ref "J5") (pin "13") (pinfunction "13_13") (pintype "passive"))
    )
    (net (code "251") (name "unconnected-(J5-Pad14)") (class "Default")
      (node (ref "J5") (pin "14") (pinfunction "14_14") (pintype "passive"))
    )
    (net (code "252") (name "unconnected-(J5-Pad15)") (class "Default")
      (node (ref "J5") (pin "15") (pinfunction "15_15") (pintype "passive"))
    )
    (net (code "253") (name "unconnected-(J5-Pad16)") (class "Default")
      (node (ref "J5") (pin "16") (pinfunction "16_16") (pintype "passive"))
    )
    (net (code "254") (name "unconnected-(J5-Pad17)") (class "Default")
      (node (ref "J5") (pin "17") (pinfunction "17_17") (pintype "passive"))
    )
    (net (code "255") (name "unconnected-(J5-Pad18)") (class "Default")
      (node (ref "J5") (pin "18") (pinfunction "18_18") (pintype "passive"))
    )
    (net (code "256") (name "unconnected-(J5-Pad19)") (class "Default")
      (node (ref "J5") (pin "19") (pinfunction "19_19") (pintype "passive"))
    )
    (net (code "257") (name "unconnected-(J5-Pad20)") (class "Default")
      (node (ref "J5") (pin "20") (pinfunction "20_20") (pintype "passive"))
    )
    (net (code "258") (name "unconnected-(J5-Pad21)") (class "Default")
      (node (ref "J5") (pin "21") (pinfunction "21_21") (pintype "passive"))
    )
    (net (code "259") (name "unconnected-(J5-Pad22)") (class "Default")
      (node (ref "J5") (pin "22") (pinfunction "22_22") (pintype "passive"))
    )
    (net (code "260") (name "unconnected-(J5-Pad23)") (class "Default")
      (node (ref "J5") (pin "23") (pinfunction "23_23") (pintype "passive"))
    )
    (net (code "261") (name "unconnected-(J5-Pad24)") (class "Default")
      (node (ref "J5") (pin "24") (pinfunction "24_24") (pintype "passive"))
    )
    (net (code "262") (name "unconnected-(J5-Pad25)") (class "Default")
      (node (ref "J5") (pin "25") (pinfunction "25_25") (pintype "passive"))
    )
    (net (code "263") (name "unconnected-(J5-Pad26)") (class "Default")
      (node (ref "J5") (pin "26") (pinfunction "26_26") (pintype "passive"))
    )
    (net (code "264") (name "unconnected-(J5-Pad27)") (class "Default")
      (node (ref "J5") (pin "27") (pinfunction "27_27") (pintype "passive"))
    )
    (net (code "265") (name "unconnected-(J5-Pad28)") (class "Default")
      (node (ref "J5") (pin "28") (pinfunction "28_28") (pintype "passive"))
    )
    (net (code "266") (name "unconnected-(J5-Pad29)") (class "Default")
      (node (ref "J5") (pin "29") (pinfunction "29_29") (pintype "passive"))
    )
    (net (code "267") (name "unconnected-(J5-Pad30)") (class "Default")
      (node (ref "J5") (pin "30") (pinfunction "30_30") (pintype "passive"))
    )
    (net (code "268") (name "unconnected-(J5-Pad31)") (class "Default")
      (node (ref "J5") (pin "31") (pinfunction "31_31") (pintype "passive"))
    )
    (net (code "269") (name "unconnected-(J5-Pad41)") (class "Default")
      (node (ref "J5") (pin "41") (pinfunction "41_41") (pintype "passive"))
    )
    (net (code "270") (name "unconnected-(J5-Pad42)") (class "Default")
      (node (ref "J5") (pin "42") (pinfunction "42_42") (pintype "passive"))
    )
    (net (code "271") (name "unconnected-(J5-Pad43)") (class "Default")
      (node (ref "J5") (pin "43") (pinfunction "43_43") (pintype "passive"))
    )
    (net (code "272") (name "unconnected-(J5-Pad44)") (class "Default")
      (node (ref "J5") (pin "44") (pinfunction "44_44") (pintype "passive"))
    )
    (net (code "273") (name "unconnected-(J5-Pad45)") (class "Default")
      (node (ref "J5") (pin "45") (pinfunction "45_45") (pintype "passive"))
    )
    (net (code "274") (name "unconnected-(J5-Pad46)") (class "Default")
      (node (ref "J5") (pin "46") (pinfunction "46_46") (pintype "passive"))
    )
    (net (code "275") (name "unconnected-(J5-Pad50)") (class "Default")
      (node (ref "J5") (pin "50") (pinfunction "50_50") (pintype "passive"))
    )
    (net (code "276") (name "unconnected-(J5-Pad51)") (class "Default")
      (node (ref "J5") (pin "51") (pinfunction "51_51") (pintype "passive"))
    )
    (net (code "277") (name "unconnected-(J5-Pad52)") (class "Default")
      (node (ref "J5") (pin "52") (pinfunction "52_52") (pintype "passive"))
    )
    (net (code "278") (name "unconnected-(J5-Pad53)") (class "Default")
      (node (ref "J5") (pin "53") (pinfunction "53_53") (pintype "passive"))
    )
    (net (code "279") (name "unconnected-(J5-Pad54)") (class "Default")
      (node (ref "J5") (pin "54") (pinfunction "54_54") (pintype "passive"))
    )
    (net (code "280") (name "unconnected-(J5-Pad55)") (class "Default")
      (node (ref "J5") (pin "55") (pinfunction "55_55") (pintype "passive"))
    )
    (net (code "281") (name "unconnected-(J5-Pad56)") (class "Default")
      (node (ref "J5") (pin "56") (pinfunction "56_56") (pintype "passive"))
    )
    (net (code "282") (name "unconnected-(J5-Pad57)") (class "Default")
      (node (ref "J5") (pin "57") (pinfunction "57_57") (pintype "passive"))
    )
    (net (code "283") (name "unconnected-(J5-Pad58)") (class "Default")
      (node (ref "J5") (pin "58") (pinfunction "58_58") (pintype "passive"))
    )
    (net (code "284") (name "unconnected-(J5-Pad61)") (class "Default")
      (node (ref "J5") (pin "61") (pinfunction "61_61") (pintype "passive"))
    )
    (net (code "285") (name "unconnected-(J5-Pad62)") (class "Default")
      (node (ref "J5") (pin "62") (pinfunction "62_62") (pintype "passive"))
    )
    (net (code "286") (name "unconnected-(J5-Pad63)") (class "Default")
      (node (ref "J5") (pin "63") (pinfunction "63_63") (pintype "passive"))
    )
    (net (code "287") (name "unconnected-(J5-Pad64)") (class "Default")
      (node (ref "J5") (pin "64") (pinfunction "64_64") (pintype "passive"))
    )
    (net (code "288") (name "unconnected-(J5-Pad65)") (class "Default")
      (node (ref "J5") (pin "65") (pinfunction "65_65") (pintype "passive"))
    )
    (net (code "289") (name "unconnected-(J5-Pad67)") (class "Default")
      (node (ref "J5") (pin "67") (pinfunction "67_67") (pintype "passive"))
    )
    (net (code "290") (name "unconnected-(J5-Pad76)") (class "Default")
      (node (ref "J5") (pin "76") (pinfunction "76_76") (pintype "passive"))
    )
    (net (code "291") (name "unconnected-(J5-Pad84)") (class "Default")
      (node (ref "J5") (pin "84") (pinfunction "84_84") (pintype "passive"))
    )
    (net (code "292") (name "unconnected-(J5-Pad87)") (class "Default")
      (node (ref "J5") (pin "87") (pinfunction "87_87") (pintype "passive"))
    )
    (net (code "293") (name "unconnected-(J5-Pad89)") (class "Default")
      (node (ref "J5") (pin "89") (pinfunction "89_89") (pintype "passive"))
    )
    (net (code "294") (name "unconnected-(J5-Pad90)") (class "Default")
      (node (ref "J5") (pin "90") (pinfunction "90_90") (pintype "passive"))
    )
    (net (code "295") (name "unconnected-(J5-Pad95)") (class "Default")
      (node (ref "J5") (pin "95") (pinfunction "95_95") (pintype "passive"))
    )
    (net (code "296") (name "unconnected-(J5-Pad98)") (class "Default")
      (node (ref "J5") (pin "98") (pinfunction "98_98") (pintype "passive"))
    )
    (net (code "297") (name "unconnected-(J5-Pad100)") (class "Default")
      (node (ref "J5") (pin "100") (pinfunction "100_100") (pintype "passive"))
    )
    (net (code "298") (name "unconnected-(J5-Pad105)") (class "Default")
      (node (ref "J5") (pin "105") (pinfunction "105_105") (pintype "passive"))
    )
    (net (code "299") (name "unconnected-(J5-Pad107)") (class "Default")
      (node (ref "J5") (pin "107") (pinfunction "107_107") (pintype "passive"))
    )
    (net (code "300") (name "unconnected-(J5-Pad108)") (class "Default")
      (node (ref "J5") (pin "108") (pinfunction "108_108") (pintype "passive"))
    )
    (net (code "301") (name "unconnected-(J5-Pad109)") (class "Default")
      (node (ref "J5") (pin "109") (pinfunction "109_109") (pintype "passive"))
    )
    (net (code "302") (name "unconnected-(J5-Pad110)") (class "Default")
      (node (ref "J5") (pin "110") (pinfunction "110_110") (pintype "passive"))
    )
    (net (code "303") (name "unconnected-(R6-Pad4)") (class "Default")
      (node (ref "R6") (pin "4") (pinfunction "4_4") (pintype "passive"))
    )
    (net (code "304") (name "unconnected-(R6-Pad5)") (class "Default")
      (node (ref "R6") (pin "5") (pinfunction "5_5") (pintype "passive"))
    )
  )
)
